# blockoccdelay.net
KiCad netlist of a schematic drawn in EAGLE
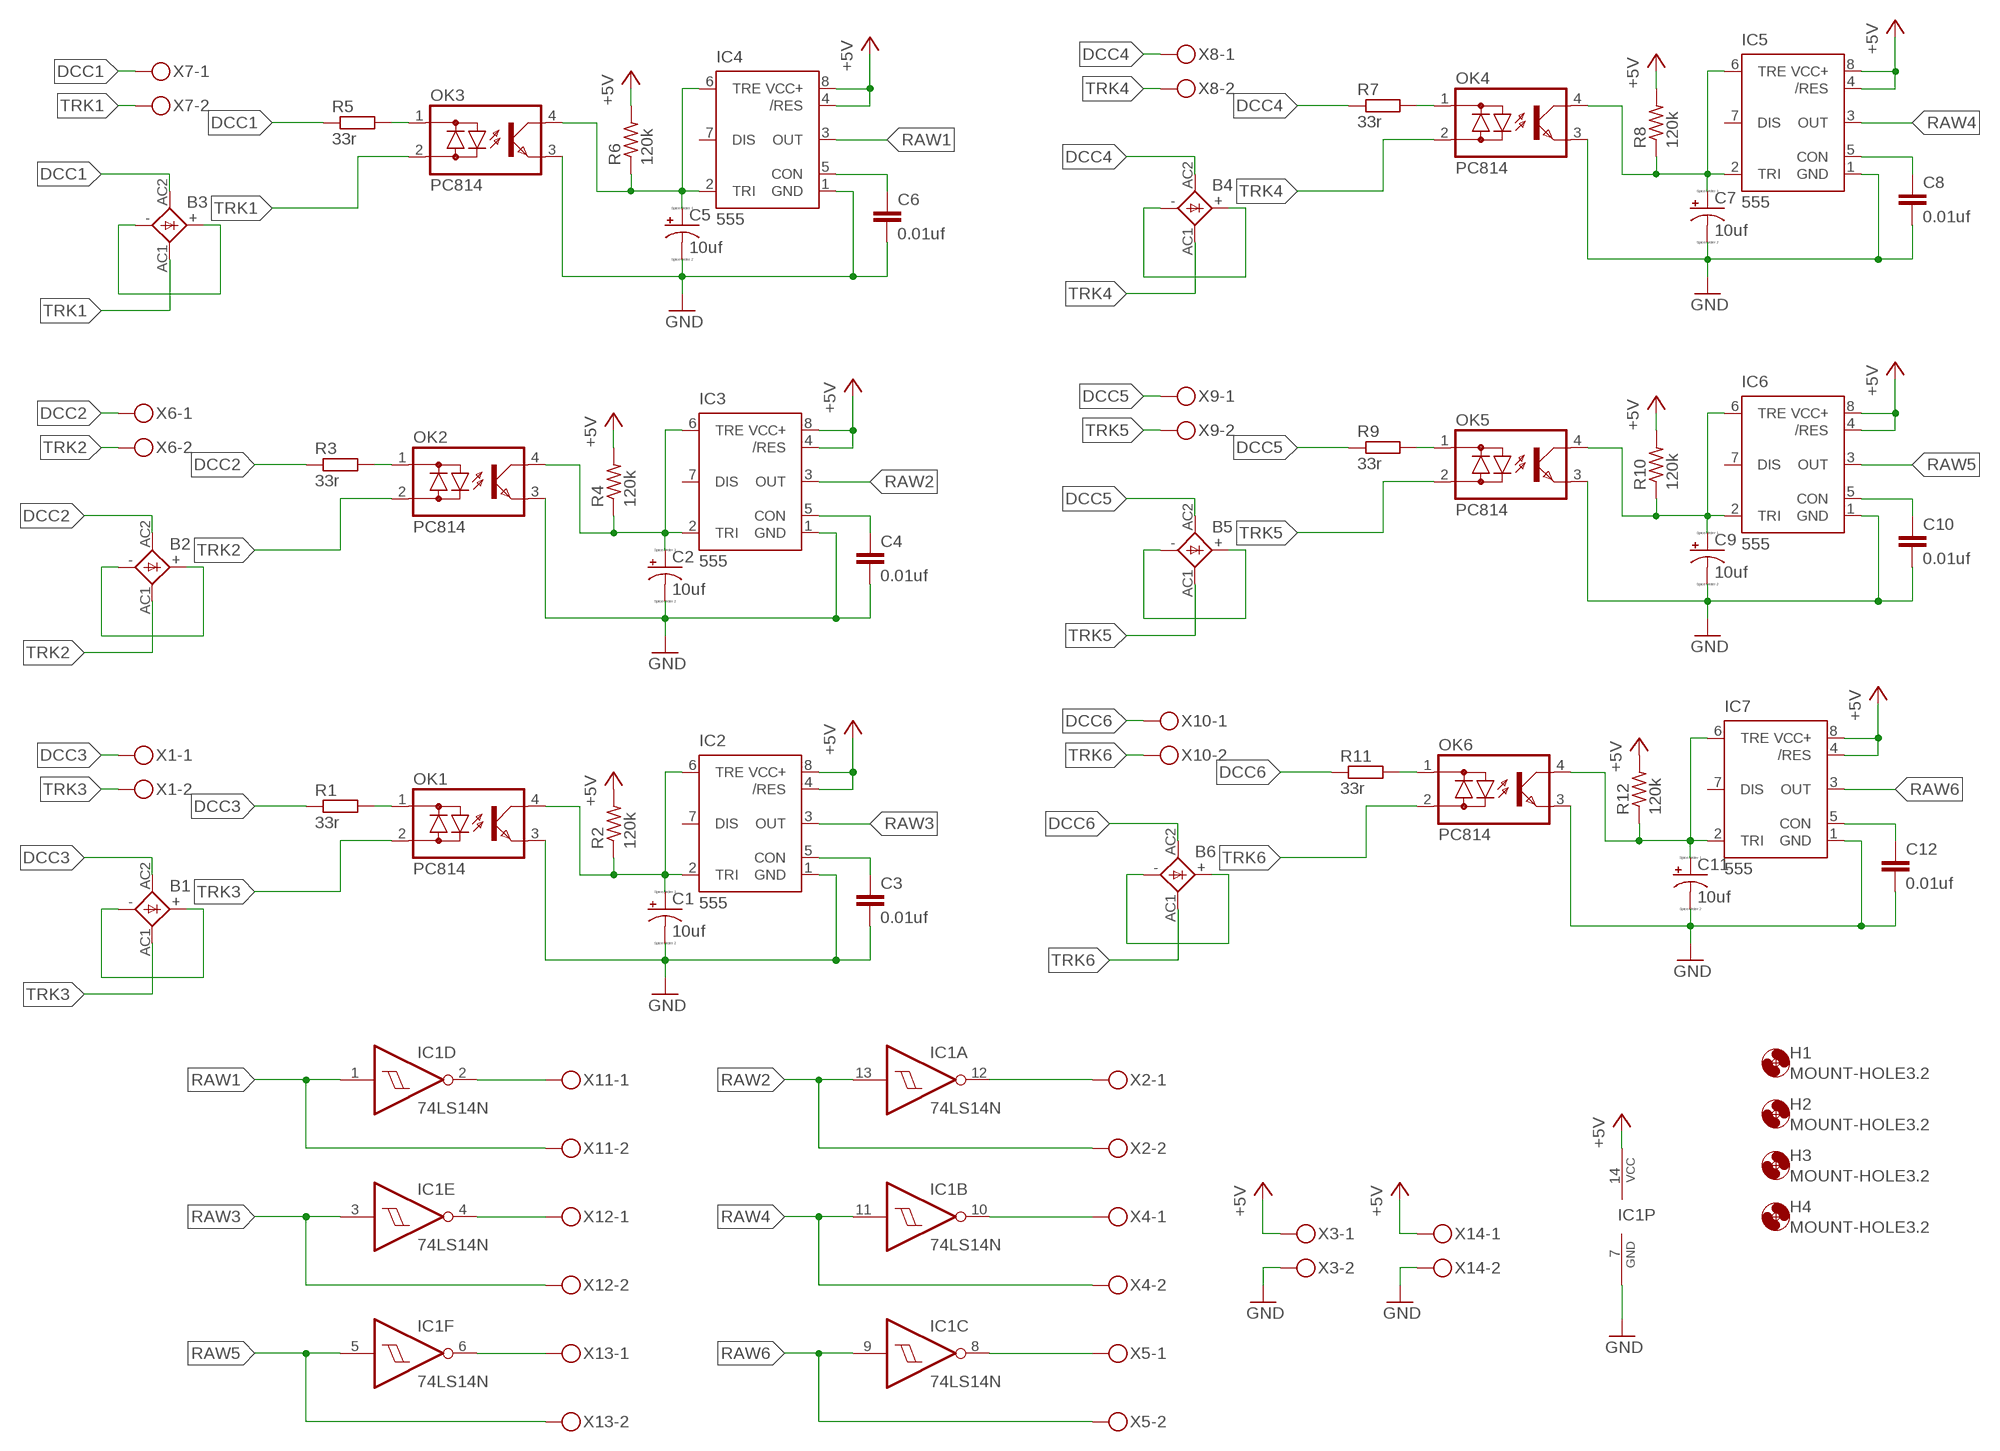
[diagram p0: schematic, sheet 1]

(export (version "E")
  (design (tool "Eeschema 10.0.6"))
  (components
    (comp (ref "B1")
      (value "GBU4")
      (footprint "eagle-import:GBU4S")
      (libsource (lib "eagle-import") (part "GBU4"))
    )
    (comp (ref "B2")
      (value "GBU4")
      (footprint "eagle-import:GBU4S")
      (libsource (lib "eagle-import") (part "GBU4"))
    )
    (comp (ref "B3")
      (value "GBU4")
      (footprint "eagle-import:GBU4S")
      (libsource (lib "eagle-import") (part "GBU4"))
    )
    (comp (ref "B4")
      (value "GBU4")
      (footprint "eagle-import:GBU4S")
      (libsource (lib "eagle-import") (part "GBU4"))
    )
    (comp (ref "B5")
      (value "GBU4")
      (footprint "eagle-import:GBU4S")
      (libsource (lib "eagle-import") (part "GBU4"))
    )
    (comp (ref "B6")
      (value "GBU4")
      (footprint "eagle-import:GBU4S")
      (libsource (lib "eagle-import") (part "GBU4"))
    )
    (comp (ref "C1")
      (value "10uf")
      (footprint "eagle-import:E2,5-6")
      (libsource (lib "eagle-import") (part "CPOL-USE2.5-6"))
    )
    (comp (ref "C2")
      (value "10uf")
      (footprint "eagle-import:E2,5-6")
      (libsource (lib "eagle-import") (part "CPOL-USE2.5-6"))
    )
    (comp (ref "C3")
      (value "0.01uf")
      (footprint "eagle-import:C050-035X075")
      (libsource (lib "eagle-import") (part "C-EU050-035X075"))
    )
    (comp (ref "C4")
      (value "0.01uf")
      (footprint "eagle-import:C050-035X075")
      (libsource (lib "eagle-import") (part "C-EU050-035X075"))
    )
    (comp (ref "C5")
      (value "10uf")
      (footprint "eagle-import:E2,5-6")
      (libsource (lib "eagle-import") (part "CPOL-USE2.5-6"))
    )
    (comp (ref "C6")
      (value "0.01uf")
      (footprint "eagle-import:C050-035X075")
      (libsource (lib "eagle-import") (part "C-EU050-035X075"))
    )
    (comp (ref "C7")
      (value "10uf")
      (footprint "eagle-import:E2,5-6")
      (libsource (lib "eagle-import") (part "CPOL-USE2.5-6"))
    )
    (comp (ref "C8")
      (value "0.01uf")
      (footprint "eagle-import:C050-035X075")
      (libsource (lib "eagle-import") (part "C-EU050-035X075"))
    )
    (comp (ref "C9")
      (value "10uf")
      (footprint "eagle-import:E2,5-6")
      (libsource (lib "eagle-import") (part "CPOL-USE2.5-6"))
    )
    (comp (ref "C10")
      (value "0.01uf")
      (footprint "eagle-import:C050-035X075")
      (libsource (lib "eagle-import") (part "C-EU050-035X075"))
    )
    (comp (ref "C11")
      (value "10uf")
      (footprint "eagle-import:E2,5-6")
      (libsource (lib "eagle-import") (part "CPOL-USE2.5-6"))
    )
    (comp (ref "C12")
      (value "0.01uf")
      (footprint "eagle-import:C050-035X075")
      (libsource (lib "eagle-import") (part "C-EU050-035X075"))
    )
    (comp (ref "H1")
      (value "MOUNT-HOLE3.2")
      (footprint "eagle-import:3,2")
      (libsource (lib "eagle-import") (part "MOUNT-HOLE3.2"))
    )
    (comp (ref "H2")
      (value "MOUNT-HOLE3.2")
      (footprint "eagle-import:3,2")
      (libsource (lib "eagle-import") (part "MOUNT-HOLE3.2"))
    )
    (comp (ref "H3")
      (value "MOUNT-HOLE3.2")
      (footprint "eagle-import:3,2")
      (libsource (lib "eagle-import") (part "MOUNT-HOLE3.2"))
    )
    (comp (ref "H4")
      (value "MOUNT-HOLE3.2")
      (footprint "eagle-import:3,2")
      (libsource (lib "eagle-import") (part "MOUNT-HOLE3.2"))
    )
    (comp (ref "IC1")
      (value "74LS14N")
      (footprint "eagle-import:DIL14")
      (libsource (lib "eagle-import") (part "7414NLS"))
    )
    (comp (ref "IC2")
      (value "555")
      (footprint "eagle-import:DIP08")
      (libsource (lib "eagle-import") (part "555P"))
    )
    (comp (ref "IC3")
      (value "555")
      (footprint "eagle-import:DIP08")
      (libsource (lib "eagle-import") (part "555P"))
    )
    (comp (ref "IC4")
      (value "555")
      (footprint "eagle-import:DIP08")
      (libsource (lib "eagle-import") (part "555P"))
    )
    (comp (ref "IC5")
      (value "555")
      (footprint "eagle-import:DIP08")
      (libsource (lib "eagle-import") (part "555P"))
    )
    (comp (ref "IC6")
      (value "555")
      (footprint "eagle-import:DIP08")
      (libsource (lib "eagle-import") (part "555P"))
    )
    (comp (ref "IC7")
      (value "555")
      (footprint "eagle-import:DIP08")
      (libsource (lib "eagle-import") (part "555P"))
    )
    (comp (ref "OK1")
      (value "PC814")
      (footprint "eagle-import:DIL04")
      (libsource (lib "eagle-import") (part "PC814"))
    )
    (comp (ref "OK2")
      (value "PC814")
      (footprint "eagle-import:DIL04")
      (libsource (lib "eagle-import") (part "PC814"))
    )
    (comp (ref "OK3")
      (value "PC814")
      (footprint "eagle-import:DIL04")
      (libsource (lib "eagle-import") (part "PC814"))
    )
    (comp (ref "OK4")
      (value "PC814")
      (footprint "eagle-import:DIL04")
      (libsource (lib "eagle-import") (part "PC814"))
    )
    (comp (ref "OK5")
      (value "PC814")
      (footprint "eagle-import:DIL04")
      (libsource (lib "eagle-import") (part "PC814"))
    )
    (comp (ref "OK6")
      (value "PC814")
      (footprint "eagle-import:DIL04")
      (libsource (lib "eagle-import") (part "PC814"))
    )
    (comp (ref "R1")
      (value "33r")
      (footprint "eagle-import:0207_2V")
      (libsource (lib "eagle-import") (part "R-EU_0207/2V"))
    )
    (comp (ref "R2")
      (value "120k")
      (footprint "eagle-import:0309V")
      (libsource (lib "eagle-import") (part "R-US_0309/V"))
    )
    (comp (ref "R3")
      (value "33r")
      (footprint "eagle-import:0207_2V")
      (libsource (lib "eagle-import") (part "R-EU_0207/2V"))
    )
    (comp (ref "R4")
      (value "120k")
      (footprint "eagle-import:0309V")
      (libsource (lib "eagle-import") (part "R-US_0309/V"))
    )
    (comp (ref "R5")
      (value "33r")
      (footprint "eagle-import:0207_2V")
      (libsource (lib "eagle-import") (part "R-EU_0207/2V"))
    )
    (comp (ref "R6")
      (value "120k")
      (footprint "eagle-import:0309V")
      (libsource (lib "eagle-import") (part "R-US_0309/V"))
    )
    (comp (ref "R7")
      (value "33r")
      (footprint "eagle-import:0207_2V")
      (libsource (lib "eagle-import") (part "R-EU_0207/2V"))
    )
    (comp (ref "R8")
      (value "120k")
      (footprint "eagle-import:0309V")
      (libsource (lib "eagle-import") (part "R-US_0309/V"))
    )
    (comp (ref "R9")
      (value "33r")
      (footprint "eagle-import:0207_2V")
      (libsource (lib "eagle-import") (part "R-EU_0207/2V"))
    )
    (comp (ref "R10")
      (value "120k")
      (footprint "eagle-import:0309V")
      (libsource (lib "eagle-import") (part "R-US_0309/V"))
    )
    (comp (ref "R11")
      (value "33r")
      (footprint "eagle-import:0207_2V")
      (libsource (lib "eagle-import") (part "R-EU_0207/2V"))
    )
    (comp (ref "R12")
      (value "120k")
      (footprint "eagle-import:0309V")
      (libsource (lib "eagle-import") (part "R-US_0309/V"))
    )
    (comp (ref "X1")
      (value "MKDSN1,5/2-5,08")
      (footprint "eagle-import:MKDSN1,5_2-5,08")
      (libsource (lib "eagle-import") (part "MKDSN1,5/2-5,08"))
    )
    (comp (ref "X2")
      (value "MKDSN1,5/2-5,08")
      (footprint "eagle-import:MKDSN1,5_2-5,08")
      (libsource (lib "eagle-import") (part "MKDSN1,5/2-5,08"))
    )
    (comp (ref "X3")
      (value "MKDSN1,5/2-5,08")
      (footprint "eagle-import:MKDSN1,5_2-5,08")
      (libsource (lib "eagle-import") (part "MKDSN1,5/2-5,08"))
    )
    (comp (ref "X4")
      (value "MKDSN1,5/2-5,08")
      (footprint "eagle-import:MKDSN1,5_2-5,08")
      (libsource (lib "eagle-import") (part "MKDSN1,5/2-5,08"))
    )
    (comp (ref "X5")
      (value "MKDSN1,5/2-5,08")
      (footprint "eagle-import:MKDSN1,5_2-5,08")
      (libsource (lib "eagle-import") (part "MKDSN1,5/2-5,08"))
    )
    (comp (ref "X6")
      (value "MKDSN1,5/2-5,08")
      (footprint "eagle-import:MKDSN1,5_2-5,08")
      (libsource (lib "eagle-import") (part "MKDSN1,5/2-5,08"))
    )
    (comp (ref "X7")
      (value "MKDSN1,5/2-5,08")
      (footprint "eagle-import:MKDSN1,5_2-5,08")
      (libsource (lib "eagle-import") (part "MKDSN1,5/2-5,08"))
    )
    (comp (ref "X8")
      (value "MKDSN1,5/2-5,08")
      (footprint "eagle-import:MKDSN1,5_2-5,08")
      (libsource (lib "eagle-import") (part "MKDSN1,5/2-5,08"))
    )
    (comp (ref "X9")
      (value "MKDSN1,5/2-5,08")
      (footprint "eagle-import:MKDSN1,5_2-5,08")
      (libsource (lib "eagle-import") (part "MKDSN1,5/2-5,08"))
    )
    (comp (ref "X10")
      (value "MKDSN1,5/2-5,08")
      (footprint "eagle-import:MKDSN1,5_2-5,08")
      (libsource (lib "eagle-import") (part "MKDSN1,5/2-5,08"))
    )
    (comp (ref "X11")
      (value "MKDSN1,5/2-5,08")
      (footprint "eagle-import:MKDSN1,5_2-5,08")
      (libsource (lib "eagle-import") (part "MKDSN1,5/2-5,08"))
    )
    (comp (ref "X12")
      (value "MKDSN1,5/2-5,08")
      (footprint "eagle-import:MKDSN1,5_2-5,08")
      (libsource (lib "eagle-import") (part "MKDSN1,5/2-5,08"))
    )
    (comp (ref "X13")
      (value "MKDSN1,5/2-5,08")
      (footprint "eagle-import:MKDSN1,5_2-5,08")
      (libsource (lib "eagle-import") (part "MKDSN1,5/2-5,08"))
    )
    (comp (ref "X14")
      (value "MKDSN1,5/2-5,08")
      (footprint "eagle-import:MKDSN1,5_2-5,08")
      (libsource (lib "eagle-import") (part "MKDSN1,5/2-5,08"))
    )
  )
  (nets
    (net (code "1") (name "+5V") (class "Default")
      (node (ref "IC1") (pin "14") (pinfunction "VCC_14") (pintype "power_in"))
      (node (ref "IC2") (pin "4") (pinfunction "/RES_4") (pintype "input"))
      (node (ref "IC2") (pin "8") (pinfunction "VCC+_8") (pintype "power_in"))
      (node (ref "IC3") (pin "4") (pinfunction "/RES_4") (pintype "input"))
      (node (ref "IC3") (pin "8") (pinfunction "VCC+_8") (pintype "power_in"))
      (node (ref "IC4") (pin "4") (pinfunction "/RES_4") (pintype "input"))
      (node (ref "IC4") (pin "8") (pinfunction "VCC+_8") (pintype "power_in"))
      (node (ref "IC5") (pin "4") (pinfunction "/RES_4") (pintype "input"))
      (node (ref "IC5") (pin "8") (pinfunction "VCC+_8") (pintype "power_in"))
      (node (ref "IC6") (pin "4") (pinfunction "/RES_4") (pintype "input"))
      (node (ref "IC6") (pin "8") (pinfunction "VCC+_8") (pintype "power_in"))
      (node (ref "IC7") (pin "4") (pinfunction "/RES_4") (pintype "input"))
      (node (ref "IC7") (pin "8") (pinfunction "VCC+_8") (pintype "power_in"))
      (node (ref "R10") (pin "2") (pinfunction "2_2") (pintype "passive"))
      (node (ref "R12") (pin "2") (pinfunction "2_2") (pintype "passive"))
      (node (ref "R2") (pin "2") (pinfunction "2_2") (pintype "passive"))
      (node (ref "R4") (pin "2") (pinfunction "2_2") (pintype "passive"))
      (node (ref "R6") (pin "2") (pinfunction "2_2") (pintype "passive"))
      (node (ref "R8") (pin "2") (pinfunction "2_2") (pintype "passive"))
      (node (ref "X14") (pin "1") (pinfunction "KL_1") (pintype "passive"))
      (node (ref "X3") (pin "1") (pinfunction "KL_1") (pintype "passive"))
    )
    (net (code "2") (name "DCC1") (class "Default")
      (node (ref "B3") (pin "AC2") (pinfunction "AC1_AC2") (pintype "passive"))
      (node (ref "R5") (pin "1") (pinfunction "1_1") (pintype "passive"))
      (node (ref "X7") (pin "1") (pinfunction "KL_1") (pintype "passive"))
    )
    (net (code "3") (name "DCC2") (class "Default")
      (node (ref "B2") (pin "AC2") (pinfunction "AC1_AC2") (pintype "passive"))
      (node (ref "R3") (pin "1") (pinfunction "1_1") (pintype "passive"))
      (node (ref "X6") (pin "1") (pinfunction "KL_1") (pintype "passive"))
    )
    (net (code "4") (name "DCC3") (class "Default")
      (node (ref "B1") (pin "AC2") (pinfunction "AC1_AC2") (pintype "passive"))
      (node (ref "R1") (pin "1") (pinfunction "1_1") (pintype "passive"))
      (node (ref "X1") (pin "1") (pinfunction "KL_1") (pintype "passive"))
    )
    (net (code "5") (name "DCC4") (class "Default")
      (node (ref "B4") (pin "AC2") (pinfunction "AC1_AC2") (pintype "passive"))
      (node (ref "R7") (pin "1") (pinfunction "1_1") (pintype "passive"))
      (node (ref "X8") (pin "1") (pinfunction "KL_1") (pintype "passive"))
    )
    (net (code "6") (name "DCC5") (class "Default")
      (node (ref "B5") (pin "AC2") (pinfunction "AC1_AC2") (pintype "passive"))
      (node (ref "R9") (pin "1") (pinfunction "1_1") (pintype "passive"))
      (node (ref "X9") (pin "1") (pinfunction "KL_1") (pintype "passive"))
    )
    (net (code "7") (name "DCC6") (class "Default")
      (node (ref "B6") (pin "AC2") (pinfunction "AC1_AC2") (pintype "passive"))
      (node (ref "R11") (pin "1") (pinfunction "1_1") (pintype "passive"))
      (node (ref "X10") (pin "1") (pinfunction "KL_1") (pintype "passive"))
    )
    (net (code "8") (name "GND") (class "Default")
      (node (ref "C1") (pin "-") (pinfunction "-_-") (pintype "passive"))
      (node (ref "C10") (pin "2") (pinfunction "2_2") (pintype "passive"))
      (node (ref "C11") (pin "-") (pinfunction "-_-") (pintype "passive"))
      (node (ref "C12") (pin "2") (pinfunction "2_2") (pintype "passive"))
      (node (ref "C2") (pin "-") (pinfunction "-_-") (pintype "passive"))
      (node (ref "C3") (pin "2") (pinfunction "2_2") (pintype "passive"))
      (node (ref "C4") (pin "2") (pinfunction "2_2") (pintype "passive"))
      (node (ref "C5") (pin "-") (pinfunction "-_-") (pintype "passive"))
      (node (ref "C6") (pin "2") (pinfunction "2_2") (pintype "passive"))
      (node (ref "C7") (pin "-") (pinfunction "-_-") (pintype "passive"))
      (node (ref "C8") (pin "2") (pinfunction "2_2") (pintype "passive"))
      (node (ref "C9") (pin "-") (pinfunction "-_-") (pintype "passive"))
      (node (ref "IC1") (pin "7") (pinfunction "GND_7") (pintype "power_in"))
      (node (ref "IC2") (pin "1") (pinfunction "GND_1") (pintype "power_in"))
      (node (ref "IC3") (pin "1") (pinfunction "GND_1") (pintype "power_in"))
      (node (ref "IC4") (pin "1") (pinfunction "GND_1") (pintype "power_in"))
      (node (ref "IC5") (pin "1") (pinfunction "GND_1") (pintype "power_in"))
      (node (ref "IC6") (pin "1") (pinfunction "GND_1") (pintype "power_in"))
      (node (ref "IC7") (pin "1") (pinfunction "GND_1") (pintype "power_in"))
      (node (ref "OK1") (pin "3") (pinfunction "E_3") (pintype "passive"))
      (node (ref "OK2") (pin "3") (pinfunction "E_3") (pintype "passive"))
      (node (ref "OK3") (pin "3") (pinfunction "E_3") (pintype "passive"))
      (node (ref "OK4") (pin "3") (pinfunction "E_3") (pintype "passive"))
      (node (ref "OK5") (pin "3") (pinfunction "E_3") (pintype "passive"))
      (node (ref "OK6") (pin "3") (pinfunction "E_3") (pintype "passive"))
      (node (ref "X14") (pin "2") (pinfunction "KL_2") (pintype "passive"))
      (node (ref "X3") (pin "2") (pinfunction "KL_2") (pintype "passive"))
    )
    (net (code "9") (name "Net-(B1-Pad+)") (class "Default")
      (node (ref "B1") (pin "+") (pinfunction "+_+") (pintype "passive"))
      (node (ref "B1") (pin "-") (pinfunction "-_-") (pintype "passive"))
    )
    (net (code "10") (name "Net-(B2-Pad+)") (class "Default")
      (node (ref "B2") (pin "+") (pinfunction "+_+") (pintype "passive"))
      (node (ref "B2") (pin "-") (pinfunction "-_-") (pintype "passive"))
    )
    (net (code "11") (name "Net-(B3-Pad+)") (class "Default")
      (node (ref "B3") (pin "+") (pinfunction "+_+") (pintype "passive"))
      (node (ref "B3") (pin "-") (pinfunction "-_-") (pintype "passive"))
    )
    (net (code "12") (name "Net-(B4-Pad+)") (class "Default")
      (node (ref "B4") (pin "+") (pinfunction "+_+") (pintype "passive"))
      (node (ref "B4") (pin "-") (pinfunction "-_-") (pintype "passive"))
    )
    (net (code "13") (name "Net-(B5-Pad+)") (class "Default")
      (node (ref "B5") (pin "+") (pinfunction "+_+") (pintype "passive"))
      (node (ref "B5") (pin "-") (pinfunction "-_-") (pintype "passive"))
    )
    (net (code "14") (name "Net-(B6-Pad+)") (class "Default")
      (node (ref "B6") (pin "+") (pinfunction "+_+") (pintype "passive"))
      (node (ref "B6") (pin "-") (pinfunction "-_-") (pintype "passive"))
    )
    (net (code "15") (name "Net-(IC1A-O)") (class "Default")
      (node (ref "IC1") (pin "12") (pinfunction "O_12") (pintype "output"))
      (node (ref "X2") (pin "1") (pinfunction "KL_1") (pintype "passive"))
    )
    (net (code "16") (name "Net-(IC1B-O)") (class "Default")
      (node (ref "IC1") (pin "10") (pinfunction "O_10") (pintype "output"))
      (node (ref "X4") (pin "1") (pinfunction "KL_1") (pintype "passive"))
    )
    (net (code "17") (name "Net-(IC1C-O)") (class "Default")
      (node (ref "IC1") (pin "8") (pinfunction "O_8") (pintype "output"))
      (node (ref "X5") (pin "1") (pinfunction "KL_1") (pintype "passive"))
    )
    (net (code "18") (name "Net-(IC1D-O)") (class "Default")
      (node (ref "IC1") (pin "2") (pinfunction "O_2") (pintype "output"))
      (node (ref "X11") (pin "1") (pinfunction "KL_1") (pintype "passive"))
    )
    (net (code "19") (name "Net-(IC1E-O)") (class "Default")
      (node (ref "IC1") (pin "4") (pinfunction "O_4") (pintype "output"))
      (node (ref "X12") (pin "1") (pinfunction "KL_1") (pintype "passive"))
    )
    (net (code "20") (name "Net-(IC1F-O)") (class "Default")
      (node (ref "IC1") (pin "6") (pinfunction "O_6") (pintype "output"))
      (node (ref "X13") (pin "1") (pinfunction "KL_1") (pintype "passive"))
    )
    (net (code "21") (name "Net-(IC2-CON)") (class "Default")
      (node (ref "C3") (pin "1") (pinfunction "1_1") (pintype "passive"))
      (node (ref "IC2") (pin "5") (pinfunction "CON_5") (pintype "input"))
    )
    (net (code "22") (name "Net-(IC2-TRE)") (class "Default")
      (node (ref "C1") (pin "+") (pinfunction "+_+") (pintype "passive"))
      (node (ref "IC2") (pin "2") (pinfunction "TRI_2") (pintype "input"))
      (node (ref "IC2") (pin "6") (pinfunction "TRE_6") (pintype "input"))
      (node (ref "OK1") (pin "4") (pinfunction "C_4") (pintype "passive"))
      (node (ref "R2") (pin "1") (pinfunction "1_1") (pintype "passive"))
    )
    (net (code "23") (name "Net-(IC3-CON)") (class "Default")
      (node (ref "C4") (pin "1") (pinfunction "1_1") (pintype "passive"))
      (node (ref "IC3") (pin "5") (pinfunction "CON_5") (pintype "input"))
    )
    (net (code "24") (name "Net-(IC3-TRE)") (class "Default")
      (node (ref "C2") (pin "+") (pinfunction "+_+") (pintype "passive"))
      (node (ref "IC3") (pin "2") (pinfunction "TRI_2") (pintype "input"))
      (node (ref "IC3") (pin "6") (pinfunction "TRE_6") (pintype "input"))
      (node (ref "OK2") (pin "4") (pinfunction "C_4") (pintype "passive"))
      (node (ref "R4") (pin "1") (pinfunction "1_1") (pintype "passive"))
    )
    (net (code "25") (name "Net-(IC4-CON)") (class "Default")
      (node (ref "C6") (pin "1") (pinfunction "1_1") (pintype "passive"))
      (node (ref "IC4") (pin "5") (pinfunction "CON_5") (pintype "input"))
    )
    (net (code "26") (name "Net-(IC4-TRE)") (class "Default")
      (node (ref "C5") (pin "+") (pinfunction "+_+") (pintype "passive"))
      (node (ref "IC4") (pin "2") (pinfunction "TRI_2") (pintype "input"))
      (node (ref "IC4") (pin "6") (pinfunction "TRE_6") (pintype "input"))
      (node (ref "OK3") (pin "4") (pinfunction "C_4") (pintype "passive"))
      (node (ref "R6") (pin "1") (pinfunction "1_1") (pintype "passive"))
    )
    (net (code "27") (name "Net-(IC5-CON)") (class "Default")
      (node (ref "C8") (pin "1") (pinfunction "1_1") (pintype "passive"))
      (node (ref "IC5") (pin "5") (pinfunction "CON_5") (pintype "input"))
    )
    (net (code "28") (name "Net-(IC5-TRE)") (class "Default")
      (node (ref "C7") (pin "+") (pinfunction "+_+") (pintype "passive"))
      (node (ref "IC5") (pin "2") (pinfunction "TRI_2") (pintype "input"))
      (node (ref "IC5") (pin "6") (pinfunction "TRE_6") (pintype "input"))
      (node (ref "OK4") (pin "4") (pinfunction "C_4") (pintype "passive"))
      (node (ref "R8") (pin "1") (pinfunction "1_1") (pintype "passive"))
    )
    (net (code "29") (name "Net-(IC6-CON)") (class "Default")
      (node (ref "C10") (pin "1") (pinfunction "1_1") (pintype "passive"))
      (node (ref "IC6") (pin "5") (pinfunction "CON_5") (pintype "input"))
    )
    (net (code "30") (name "Net-(IC6-TRE)") (class "Default")
      (node (ref "C9") (pin "+") (pinfunction "+_+") (pintype "passive"))
      (node (ref "IC6") (pin "2") (pinfunction "TRI_2") (pintype "input"))
      (node (ref "IC6") (pin "6") (pinfunction "TRE_6") (pintype "input"))
      (node (ref "OK5") (pin "4") (pinfunction "C_4") (pintype "passive"))
      (node (ref "R10") (pin "1") (pinfunction "1_1") (pintype "passive"))
    )
    (net (code "31") (name "Net-(IC7-CON)") (class "Default")
      (node (ref "C12") (pin "1") (pinfunction "1_1") (pintype "passive"))
      (node (ref "IC7") (pin "5") (pinfunction "CON_5") (pintype "input"))
    )
    (net (code "32") (name "Net-(IC7-TRE)") (class "Default")
      (node (ref "C11") (pin "+") (pinfunction "+_+") (pintype "passive"))
      (node (ref "IC7") (pin "2") (pinfunction "TRI_2") (pintype "input"))
      (node (ref "IC7") (pin "6") (pinfunction "TRE_6") (pintype "input"))
      (node (ref "OK6") (pin "4") (pinfunction "C_4") (pintype "passive"))
      (node (ref "R12") (pin "1") (pinfunction "1_1") (pintype "passive"))
    )
    (net (code "33") (name "Net-(OK1-AC1)") (class "Default")
      (node (ref "OK1") (pin "1") (pinfunction "AC1_1") (pintype "passive"))
      (node (ref "R1") (pin "2") (pinfunction "2_2") (pintype "passive"))
    )
    (net (code "34") (name "Net-(OK2-AC1)") (class "Default")
      (node (ref "OK2") (pin "1") (pinfunction "AC1_1") (pintype "passive"))
      (node (ref "R3") (pin "2") (pinfunction "2_2") (pintype "passive"))
    )
    (net (code "35") (name "Net-(OK3-AC1)") (class "Default")
      (node (ref "OK3") (pin "1") (pinfunction "AC1_1") (pintype "passive"))
      (node (ref "R5") (pin "2") (pinfunction "2_2") (pintype "passive"))
    )
    (net (code "36") (name "Net-(OK4-AC1)") (class "Default")
      (node (ref "OK4") (pin "1") (pinfunction "AC1_1") (pintype "passive"))
      (node (ref "R7") (pin "2") (pinfunction "2_2") (pintype "passive"))
    )
    (net (code "37") (name "Net-(OK5-AC1)") (class "Default")
      (node (ref "OK5") (pin "1") (pinfunction "AC1_1") (pintype "passive"))
      (node (ref "R9") (pin "2") (pinfunction "2_2") (pintype "passive"))
    )
    (net (code "38") (name "Net-(OK6-AC1)") (class "Default")
      (node (ref "OK6") (pin "1") (pinfunction "AC1_1") (pintype "passive"))
      (node (ref "R11") (pin "2") (pinfunction "2_2") (pintype "passive"))
    )
    (net (code "39") (name "RAW1") (class "Default")
      (node (ref "IC1") (pin "1") (pinfunction "I_1") (pintype "input"))
      (node (ref "IC4") (pin "3") (pinfunction "OUT_3") (pintype "output"))
      (node (ref "X11") (pin "2") (pinfunction "KL_2") (pintype "passive"))
    )
    (net (code "40") (name "RAW2") (class "Default")
      (node (ref "IC1") (pin "13") (pinfunction "I_13") (pintype "input"))
      (node (ref "IC3") (pin "3") (pinfunction "OUT_3") (pintype "output"))
      (node (ref "X2") (pin "2") (pinfunction "KL_2") (pintype "passive"))
    )
    (net (code "41") (name "RAW3") (class "Default")
      (node (ref "IC1") (pin "3") (pinfunction "I_3") (pintype "input"))
      (node (ref "IC2") (pin "3") (pinfunction "OUT_3") (pintype "output"))
      (node (ref "X12") (pin "2") (pinfunction "KL_2") (pintype "passive"))
    )
    (net (code "42") (name "RAW4") (class "Default")
      (node (ref "IC1") (pin "11") (pinfunction "I_11") (pintype "input"))
      (node (ref "IC5") (pin "3") (pinfunction "OUT_3") (pintype "output"))
      (node (ref "X4") (pin "2") (pinfunction "KL_2") (pintype "passive"))
    )
    (net (code "43") (name "RAW5") (class "Default")
      (node (ref "IC1") (pin "5") (pinfunction "I_5") (pintype "input"))
      (node (ref "IC6") (pin "3") (pinfunction "OUT_3") (pintype "output"))
      (node (ref "X13") (pin "2") (pinfunction "KL_2") (pintype "passive"))
    )
    (net (code "44") (name "RAW6") (class "Default")
      (node (ref "IC1") (pin "9") (pinfunction "I_9") (pintype "input"))
      (node (ref "IC7") (pin "3") (pinfunction "OUT_3") (pintype "output"))
      (node (ref "X5") (pin "2") (pinfunction "KL_2") (pintype "passive"))
    )
    (net (code "45") (name "TRK1") (class "Default")
      (node (ref "B3") (pin "AC1") (pinfunction "AC2_AC1") (pintype "passive"))
      (node (ref "OK3") (pin "2") (pinfunction "AC2_2") (pintype "passive"))
      (node (ref "X7") (pin "2") (pinfunction "KL_2") (pintype "passive"))
    )
    (net (code "46") (name "TRK2") (class "Default")
      (node (ref "B2") (pin "AC1") (pinfunction "AC2_AC1") (pintype "passive"))
      (node (ref "OK2") (pin "2") (pinfunction "AC2_2") (pintype "passive"))
      (node (ref "X6") (pin "2") (pinfunction "KL_2") (pintype "passive"))
    )
    (net (code "47") (name "TRK3") (class "Default")
      (node (ref "B1") (pin "AC1") (pinfunction "AC2_AC1") (pintype "passive"))
      (node (ref "OK1") (pin "2") (pinfunction "AC2_2") (pintype "passive"))
      (node (ref "X1") (pin "2") (pinfunction "KL_2") (pintype "passive"))
    )
    (net (code "48") (name "TRK4") (class "Default")
      (node (ref "B4") (pin "AC1") (pinfunction "AC2_AC1") (pintype "passive"))
      (node (ref "OK4") (pin "2") (pinfunction "AC2_2") (pintype "passive"))
      (node (ref "X8") (pin "2") (pinfunction "KL_2") (pintype "passive"))
    )
    (net (code "49") (name "TRK5") (class "Default")
      (node (ref "B5") (pin "AC1") (pinfunction "AC2_AC1") (pintype "passive"))
      (node (ref "OK5") (pin "2") (pinfunction "AC2_2") (pintype "passive"))
      (node (ref "X9") (pin "2") (pinfunction "KL_2") (pintype "passive"))
    )
    (net (code "50") (name "TRK6") (class "Default")
      (node (ref "B6") (pin "AC1") (pinfunction "AC2_AC1") (pintype "passive"))
      (node (ref "OK6") (pin "2") (pinfunction "AC2_2") (pintype "passive"))
      (node (ref "X10") (pin "2") (pinfunction "KL_2") (pintype "passive"))
    )
    (net (code "51") (name "unconnected-(IC2-DIS-Pad7)") (class "Default")
      (node (ref "IC2") (pin "7") (pinfunction "DIS_7") (pintype "input"))
    )
    (net (code "52") (name "unconnected-(IC3-DIS-Pad7)") (class "Default")
      (node (ref "IC3") (pin "7") (pinfunction "DIS_7") (pintype "input"))
    )
    (net (code "53") (name "unconnected-(IC4-DIS-Pad7)") (class "Default")
      (node (ref "IC4") (pin "7") (pinfunction "DIS_7") (pintype "input"))
    )
    (net (code "54") (name "unconnected-(IC5-DIS-Pad7)") (class "Default")
      (node (ref "IC5") (pin "7") (pinfunction "DIS_7") (pintype "input"))
    )
    (net (code "55") (name "unconnected-(IC6-DIS-Pad7)") (class "Default")
      (node (ref "IC6") (pin "7") (pinfunction "DIS_7") (pintype "input"))
    )
    (net (code "56") (name "unconnected-(IC7-DIS-Pad7)") (class "Default")
      (node (ref "IC7") (pin "7") (pinfunction "DIS_7") (pintype "input"))
    )
  )
)
